# BoardIF.net
KiCad netlist of a schematic drawn in Altium Designer
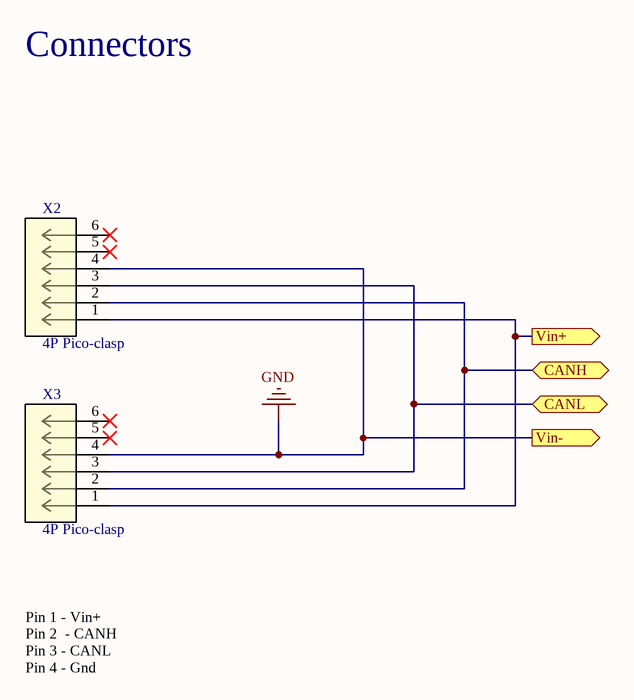
[diagram p0: BoardIF.SchDoc]

(export (version "E")
  (design (tool "Eeschema 10.0.6"))
  (components
    (comp (ref "X2")
      (value "4P Pico-clasp")
      (footprint "CON_2023960407")
      (description "Conn Shrouded Header (4 Sides) HDR 4 POS 1mm Solder RA SMD Pico-Clasp™ T/R")
      (fields (field (name "MANUFACTURER") "Molex") (field (name "MANUFACTURER PART NUMBER") "202396-0407"))
      (libsource (lib "Schlib1") (part "202396-0407"))
    )
    (comp (ref "X3")
      (value "4P Pico-clasp")
      (footprint "CON_2023960407")
      (description "Conn Shrouded Header (4 Sides) HDR 4 POS 1mm Solder RA SMD Pico-Clasp™ T/R")
      (fields (field (name "MANUFACTURER") "Molex") (field (name "MANUFACTURER PART NUMBER") "202396-0407"))
      (libsource (lib "Schlib1") (part "202396-0407"))
    )
  )
  (nets
    (net (code "1") (name "/CANH") (class "Default")
      (node (ref "X2") (pin "2") (pinfunction "2_2") (pintype "passive"))
      (node (ref "X3") (pin "2") (pinfunction "2_2") (pintype "passive"))
    )
    (net (code "2") (name "/CANL") (class "Default")
      (node (ref "X2") (pin "3") (pinfunction "3_3") (pintype "passive"))
      (node (ref "X3") (pin "3") (pinfunction "3_3") (pintype "passive"))
    )
    (net (code "3") (name "/Vin+") (class "Default")
      (node (ref "X2") (pin "1") (pinfunction "1_1") (pintype "passive"))
      (node (ref "X3") (pin "1") (pinfunction "1_1") (pintype "passive"))
    )
    (net (code "4") (name "GND") (class "Default")
      (node (ref "X2") (pin "4") (pinfunction "4_4") (pintype "passive"))
      (node (ref "X3") (pin "4") (pinfunction "4_4") (pintype "passive"))
    )
    (net (code "5") (name "unconnected-(X2-Pad5)") (class "Default")
      (node (ref "X2") (pin "5") (pinfunction "5_5") (pintype "passive+no_connect"))
    )
    (net (code "6") (name "unconnected-(X2-Pad6)") (class "Default")
      (node (ref "X2") (pin "6") (pinfunction "6_6") (pintype "passive+no_connect"))
    )
    (net (code "7") (name "unconnected-(X3-Pad5)") (class "Default")
      (node (ref "X3") (pin "5") (pinfunction "5_5") (pintype "passive+no_connect"))
    )
    (net (code "8") (name "unconnected-(X3-Pad6)") (class "Default")
      (node (ref "X3") (pin "6") (pinfunction "6_6") (pintype "passive+no_connect"))
    )
  )
)
